# RIAA.net
KiCad netlist of a schematic drawn in Altium Designer
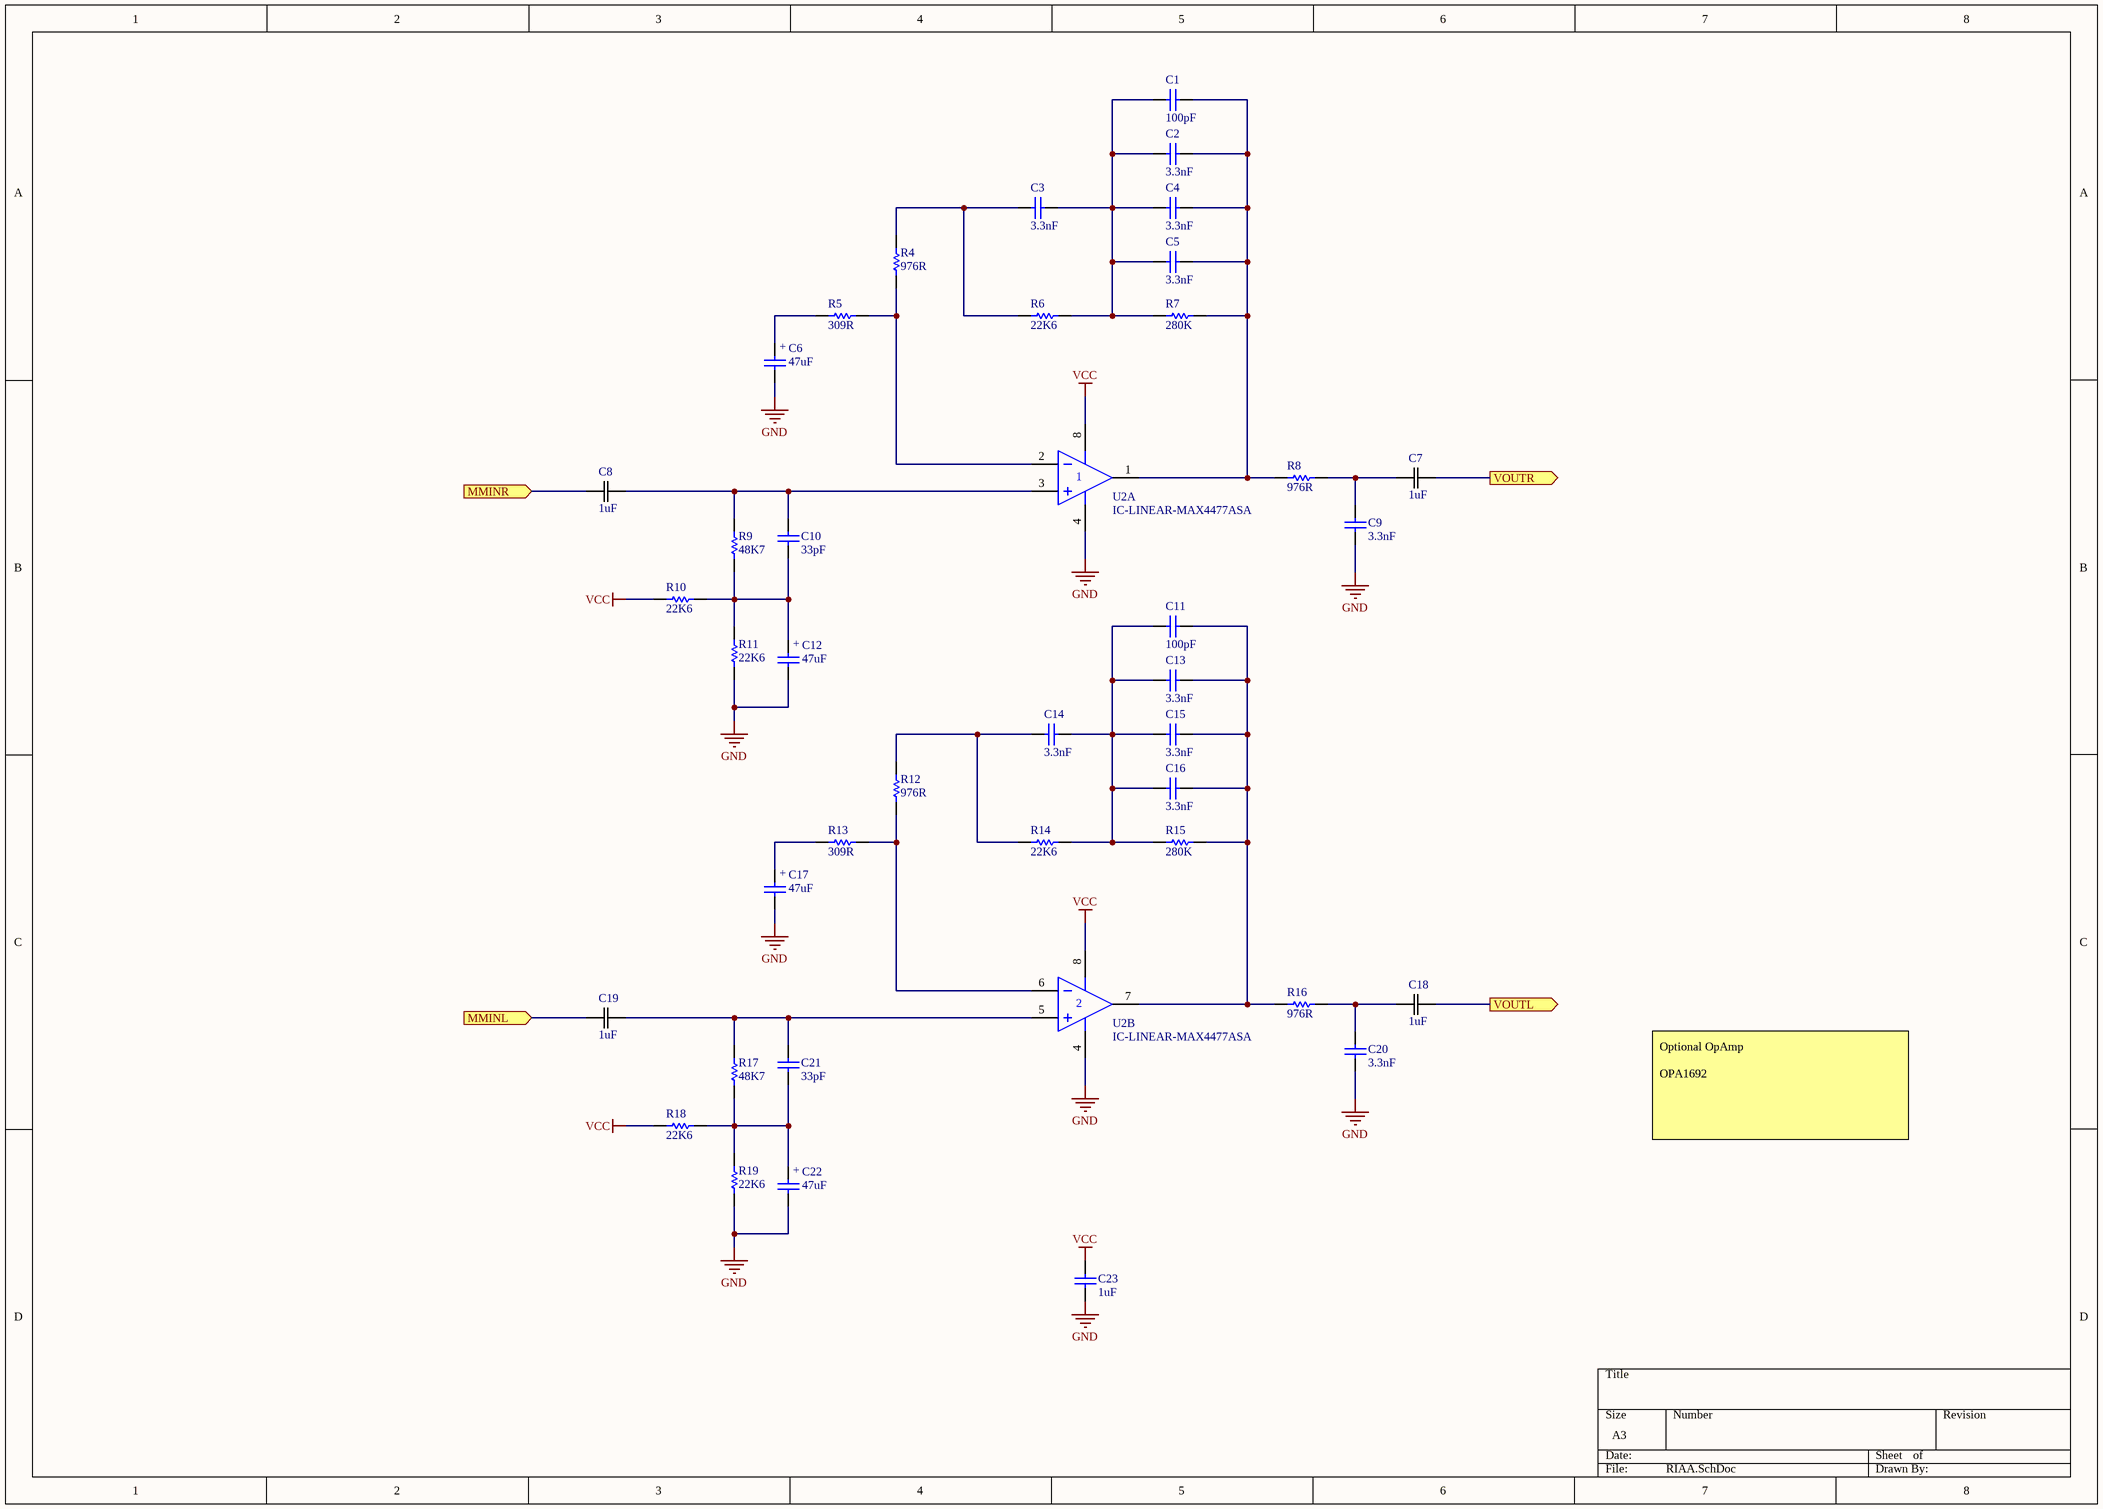
[diagram p0: RIAA.SchDoc]

(export (version "E")
  (design (tool "Eeschema 10.0.6"))
  (components
    (comp (ref "C1")
      (value "100pF")
      (footprint "CAPC0402(1005)33_L")
      (description "0402 100pF ±5% 50V C0G，NP0")
      (fields (field (name "MPN") "0402CG101J500NT") (field (name "VOLTAGE") "50V"))
      (libsource (lib "seeed") (part "CAP_100pF_0402"))
    )
    (comp (ref "C2")
      (value "3.3nF")
      (footprint "CAPC0603(1608)55_L")
      (description "0603 3.3nF ±5% 50V C0G(NPO) H=0.8mm")
      (fields (field (name "MPN") "CL10C332JB8NFNC") (field (name "VOLTAGE") "50V"))
      (libsource (lib "seeed") (part "CAP_3.3nF_0603"))
    )
    (comp (ref "C3")
      (value "3.3nF")
      (footprint "CAPC0603(1608)55_L")
      (description "0603 3.3nF ±5% 50V C0G(NPO) H=0.8mm")
      (fields (field (name "MPN") "CL10C332JB8NFNC") (field (name "VOLTAGE") "50V"))
      (libsource (lib "seeed") (part "CAP_3.3nF_0603"))
    )
    (comp (ref "C4")
      (value "3.3nF")
      (footprint "CAPC0603(1608)55_L")
      (description "0603 3.3nF ±5% 50V C0G(NPO) H=0.8mm")
      (fields (field (name "MPN") "CL10C332JB8NFNC") (field (name "VOLTAGE") "50V"))
      (libsource (lib "seeed") (part "CAP_3.3nF_0603"))
    )
    (comp (ref "C5")
      (value "3.3nF")
      (footprint "CAPC0603(1608)55_L")
      (description "0603 3.3nF ±5% 50V C0G(NPO) H=0.8mm")
      (fields (field (name "MPN") "CL10C332JB8NFNC") (field (name "VOLTAGE") "50V"))
      (libsource (lib "seeed") (part "CAP_3.3nF_0603"))
    )
    (comp (ref "C6")
      (value "47uF")
      (footprint "CAPPM3216X180N")
      (description "47µF ±10% 6.3V ESR=1.6Ω@100kHz")
      (fields (field (name "MPN") "TAJA476K006RNJ") (field (name "VOLTAGE") "6.3V"))
      (libsource (lib "seeed") (part "CAP_47uF_6.3V_1206"))
    )
    (comp (ref "C7")
      (value "1uF")
      (footprint "CAP_ECPU_G2")
      (description "1µF Film Capacitor  16V Acrylic, Metallized - Stacked 1210 (3225 Metric)")
      (fields (field (name "MPN") "ECP-U1C105MA5"))
      (libsource (lib "micun") (part "CAP-ECP-U1C105MA5"))
    )
    (comp (ref "C8")
      (value "1uF")
      (footprint "CAP_ECPU_G2")
      (description "1µF Film Capacitor  16V Acrylic, Metallized - Stacked 1210 (3225 Metric)")
      (fields (field (name "MPN") "ECP-U1C105MA5"))
      (libsource (lib "micun") (part "CAP-ECP-U1C105MA5"))
    )
    (comp (ref "C9")
      (value "3.3nF")
      (footprint "CAPC0603(1608)55_L")
      (description "0603 3.3nF ±5% 50V C0G(NPO) H=0.8mm")
      (fields (field (name "MPN") "CL10C332JB8NFNC") (field (name "VOLTAGE") "50V"))
      (libsource (lib "seeed") (part "CAP_3.3nF_0603"))
    )
    (comp (ref "C10")
      (value "33pF")
      (footprint "CAPC0402(1005)33_L")
      (description "0402 33PF ±5% 50V NPO")
      (fields (field (name "MPN") "CC0402JRNPO9BN330") (field (name "VOLTAGE") "50V"))
      (libsource (lib "seeed") (part "CAP_33pF_0402"))
    )
    (comp (ref "C11")
      (value "100pF")
      (footprint "CAPC0402(1005)33_L")
      (description "0402 100pF ±5% 50V C0G，NP0")
      (fields (field (name "MPN") "0402CG101J500NT") (field (name "VOLTAGE") "50V"))
      (libsource (lib "seeed") (part "CAP_100pF_0402"))
    )
    (comp (ref "C12")
      (value "47uF")
      (footprint "CAPPM3216X180N")
      (description "47µF ±10% 6.3V ESR=1.6Ω@100kHz")
      (fields (field (name "MPN") "TAJA476K006RNJ") (field (name "VOLTAGE") "6.3V"))
      (libsource (lib "seeed") (part "CAP_47uF_6.3V_1206"))
    )
    (comp (ref "C13")
      (value "3.3nF")
      (footprint "CAPC0603(1608)55_L")
      (description "0603 3.3nF ±5% 50V C0G(NPO) H=0.8mm")
      (fields (field (name "MPN") "CL10C332JB8NFNC") (field (name "VOLTAGE") "50V"))
      (libsource (lib "seeed") (part "CAP_3.3nF_0603"))
    )
    (comp (ref "C14")
      (value "3.3nF")
      (footprint "CAPC0603(1608)55_L")
      (description "0603 3.3nF ±5% 50V C0G(NPO) H=0.8mm")
      (fields (field (name "MPN") "CL10C332JB8NFNC") (field (name "VOLTAGE") "50V"))
      (libsource (lib "seeed") (part "CAP_3.3nF_0603"))
    )
    (comp (ref "C15")
      (value "3.3nF")
      (footprint "CAPC0603(1608)55_L")
      (description "0603 3.3nF ±5% 50V C0G(NPO) H=0.8mm")
      (fields (field (name "MPN") "CL10C332JB8NFNC") (field (name "VOLTAGE") "50V"))
      (libsource (lib "seeed") (part "CAP_3.3nF_0603"))
    )
    (comp (ref "C16")
      (value "3.3nF")
      (footprint "CAPC0603(1608)55_L")
      (description "0603 3.3nF ±5% 50V C0G(NPO) H=0.8mm")
      (fields (field (name "MPN") "CL10C332JB8NFNC") (field (name "VOLTAGE") "50V"))
      (libsource (lib "seeed") (part "CAP_3.3nF_0603"))
    )
    (comp (ref "C17")
      (value "47uF")
      (footprint "CAPPM3216X180N")
      (description "47µF ±10% 6.3V ESR=1.6Ω@100kHz")
      (fields (field (name "MPN") "TAJA476K006RNJ") (field (name "VOLTAGE") "6.3V"))
      (libsource (lib "seeed") (part "CAP_47uF_6.3V_1206"))
    )
    (comp (ref "C18")
      (value "1uF")
      (footprint "CAP_ECPU_G2")
      (description "1µF Film Capacitor  16V Acrylic, Metallized - Stacked 1210 (3225 Metric)")
      (fields (field (name "MPN") "ECP-U1C105MA5"))
      (libsource (lib "micun") (part "CAP-ECP-U1C105MA5"))
    )
    (comp (ref "C19")
      (value "1uF")
      (footprint "CAP_ECPU_G2")
      (description "1µF Film Capacitor  16V Acrylic, Metallized - Stacked 1210 (3225 Metric)")
      (fields (field (name "MPN") "ECP-U1C105MA5"))
      (libsource (lib "micun") (part "CAP-ECP-U1C105MA5"))
    )
    (comp (ref "C20")
      (value "3.3nF")
      (footprint "CAPC0603(1608)55_L")
      (description "0603 3.3nF ±5% 50V C0G(NPO) H=0.8mm")
      (fields (field (name "MPN") "CL10C332JB8NFNC") (field (name "VOLTAGE") "50V"))
      (libsource (lib "seeed") (part "CAP_3.3nF_0603"))
    )
    (comp (ref "C21")
      (value "33pF")
      (footprint "CAPC0402(1005)33_L")
      (description "0402 33PF ±5% 50V NPO")
      (fields (field (name "MPN") "CC0402JRNPO9BN330") (field (name "VOLTAGE") "50V"))
      (libsource (lib "seeed") (part "CAP_33pF_0402"))
    )
    (comp (ref "C22")
      (value "47uF")
      (footprint "CAPPM3216X180N")
      (description "47µF ±10% 6.3V ESR=1.6Ω@100kHz")
      (fields (field (name "MPN") "TAJA476K006RNJ") (field (name "VOLTAGE") "6.3V"))
      (libsource (lib "seeed") (part "CAP_47uF_6.3V_1206"))
    )
    (comp (ref "C23")
      (value "1uF")
      (footprint "CAPC0402(1005)33_L")
      (description "0402 1μF ±10% 16V X5R")
      (fields (field (name "MPN") "GRM155R61C105KA12D") (field (name "VOLTAGE") "10V"))
      (libsource (lib "seeed") (part "CAP_1uF_0402"))
    )
    (comp (ref "R4")
      (value "976R")
      (footprint "RESC0402(1005)_L")
      (description "0402 976Ω ±1% 1/16W")
      (fields (field (name "TOLERANCE") "1%") (field (name "POWER") "62.5mW"))
      (libsource (lib "seeed") (part "RES_976R_0402"))
    )
    (comp (ref "R5")
      (value "309R")
      (footprint "RESC0402(1005)_L")
      (description "0402 309Ω ±1% 1/16W")
      (fields (field (name "TOLERANCE") "1%") (field (name "POWER") "62.5mW"))
      (libsource (lib "seeed") (part "RES_309R_0402"))
    )
    (comp (ref "R6")
      (value "22K6")
      (footprint "RESC0402(1005)_L")
      (description "0402 22.6KΩ ±1% 1/16W")
      (fields (field (name "TOLERANCE") "1%") (field (name "POWER") "62.5mW"))
      (libsource (lib "seeed") (part "RES_22K6_0402"))
    )
    (comp (ref "R7")
      (value "280K")
      (footprint "RESC0402(1005)_L")
      (description "0402 280KΩ ±1% 1/16W")
      (fields (field (name "TOLERANCE") "1%") (field (name "POWER") "62.5mW"))
      (libsource (lib "seeed") (part "RES_280K_0402"))
    )
    (comp (ref "R8")
      (value "976R")
      (footprint "RESC0402(1005)_L")
      (description "0402 976Ω ±1% 1/16W")
      (fields (field (name "TOLERANCE") "1%") (field (name "POWER") "62.5mW"))
      (libsource (lib "seeed") (part "RES_976R_0402"))
    )
    (comp (ref "R9")
      (value "48K7")
      (footprint "RESC0402(1005)_L")
      (description "0402 48.7KΩ ±1% 1/16W")
      (fields (field (name "TOLERANCE") "1%") (field (name "POWER") "62.5mW"))
      (libsource (lib "seeed") (part "RES_48K7_0402"))
    )
    (comp (ref "R10")
      (value "22K6")
      (footprint "RESC0402(1005)_L")
      (description "0402 22.6KΩ ±1% 1/16W")
      (fields (field (name "TOLERANCE") "1%") (field (name "POWER") "62.5mW"))
      (libsource (lib "seeed") (part "RES_22K6_0402"))
    )
    (comp (ref "R11")
      (value "22K6")
      (footprint "RESC0402(1005)_L")
      (description "0402 22.6KΩ ±1% 1/16W")
      (fields (field (name "TOLERANCE") "1%") (field (name "POWER") "62.5mW"))
      (libsource (lib "seeed") (part "RES_22K6_0402"))
    )
    (comp (ref "R12")
      (value "976R")
      (footprint "RESC0402(1005)_L")
      (description "0402 976Ω ±1% 1/16W")
      (fields (field (name "TOLERANCE") "1%") (field (name "POWER") "62.5mW"))
      (libsource (lib "seeed") (part "RES_976R_0402"))
    )
    (comp (ref "R13")
      (value "309R")
      (footprint "RESC0402(1005)_L")
      (description "0402 309Ω ±1% 1/16W")
      (fields (field (name "TOLERANCE") "1%") (field (name "POWER") "62.5mW"))
      (libsource (lib "seeed") (part "RES_309R_0402"))
    )
    (comp (ref "R14")
      (value "22K6")
      (footprint "RESC0402(1005)_L")
      (description "0402 22.6KΩ ±1% 1/16W")
      (fields (field (name "TOLERANCE") "1%") (field (name "POWER") "62.5mW"))
      (libsource (lib "seeed") (part "RES_22K6_0402"))
    )
    (comp (ref "R15")
      (value "280K")
      (footprint "RESC0402(1005)_L")
      (description "0402 280KΩ ±1% 1/16W")
      (fields (field (name "TOLERANCE") "1%") (field (name "POWER") "62.5mW"))
      (libsource (lib "seeed") (part "RES_280K_0402"))
    )
    (comp (ref "R16")
      (value "976R")
      (footprint "RESC0402(1005)_L")
      (description "0402 976Ω ±1% 1/16W")
      (fields (field (name "TOLERANCE") "1%") (field (name "POWER") "62.5mW"))
      (libsource (lib "seeed") (part "RES_976R_0402"))
    )
    (comp (ref "R17")
      (value "48K7")
      (footprint "RESC0402(1005)_L")
      (description "0402 48.7KΩ ±1% 1/16W")
      (fields (field (name "TOLERANCE") "1%") (field (name "POWER") "62.5mW"))
      (libsource (lib "seeed") (part "RES_48K7_0402"))
    )
    (comp (ref "R18")
      (value "22K6")
      (footprint "RESC0402(1005)_L")
      (description "0402 22.6KΩ ±1% 1/16W")
      (fields (field (name "TOLERANCE") "1%") (field (name "POWER") "62.5mW"))
      (libsource (lib "seeed") (part "RES_22K6_0402"))
    )
    (comp (ref "R19")
      (value "22K6")
      (footprint "RESC0402(1005)_L")
      (description "0402 22.6KΩ ±1% 1/16W")
      (fields (field (name "TOLERANCE") "1%") (field (name "POWER") "62.5mW"))
      (libsource (lib "seeed") (part "RES_22K6_0402"))
    )
    (comp (ref "U2")
      (value "IC-LINEAR-MAX4477ASA")
      (footprint "SOIC8_N")
      (description "Dual Rail-to-Rail output  Low-Power Operational Amplifier")
      (fields (field (name "MPN") "MAX4477ASA+"))
      (libsource (lib "micun") (part "IC-LINEAR-MAX4477ASA"))
    )
  )
  (nets
    (net (code "1") (name "/MMINL") (class "Default")
      (node (ref "C19") (pin "1") (pinfunction "1_1") (pintype "passive"))
    )
    (net (code "2") (name "/MMINR") (class "Default")
      (node (ref "C8") (pin "1") (pinfunction "1_1") (pintype "passive"))
    )
    (net (code "3") (name "/VOUTL") (class "Default")
      (node (ref "C18") (pin "2") (pinfunction "2_2") (pintype "passive"))
    )
    (net (code "4") (name "/VOUTR") (class "Default")
      (node (ref "C7") (pin "2") (pinfunction "2_2") (pintype "passive"))
    )
    (net (code "5") (name "GND") (class "Default")
      (node (ref "C12") (pin "2") (pinfunction "2_2") (pintype "passive"))
      (node (ref "C17") (pin "2") (pinfunction "2_2") (pintype "passive"))
      (node (ref "C20") (pin "1") (pinfunction "1_1") (pintype "passive"))
      (node (ref "C22") (pin "2") (pinfunction "2_2") (pintype "passive"))
      (node (ref "C23") (pin "1") (pinfunction "1_1") (pintype "passive"))
      (node (ref "C6") (pin "2") (pinfunction "2_2") (pintype "passive"))
      (node (ref "C9") (pin "1") (pinfunction "1_1") (pintype "passive"))
      (node (ref "R11") (pin "2") (pinfunction "2_2") (pintype "passive"))
      (node (ref "R19") (pin "2") (pinfunction "2_2") (pintype "passive"))
      (node (ref "U2") (pin "4") (pinfunction "V-_4") (pintype "power_in"))
    )
    (net (code "6") (name "Net-(C1-Pad1)") (class "Default")
      (node (ref "C1") (pin "1") (pinfunction "1_1") (pintype "passive"))
      (node (ref "C2") (pin "1") (pinfunction "1_1") (pintype "passive"))
      (node (ref "C3") (pin "2") (pinfunction "2_2") (pintype "passive"))
      (node (ref "C4") (pin "1") (pinfunction "1_1") (pintype "passive"))
      (node (ref "C5") (pin "1") (pinfunction "1_1") (pintype "passive"))
      (node (ref "R6") (pin "2") (pinfunction "2_2") (pintype "passive"))
      (node (ref "R7") (pin "1") (pinfunction "1_1") (pintype "passive"))
    )
    (net (code "7") (name "Net-(C3-Pad1)") (class "Default")
      (node (ref "C3") (pin "1") (pinfunction "1_1") (pintype "passive"))
      (node (ref "R4") (pin "1") (pinfunction "1_1") (pintype "passive"))
      (node (ref "R6") (pin "1") (pinfunction "1_1") (pintype "passive"))
    )
    (net (code "8") (name "Net-(C6-Pad1)") (class "Default")
      (node (ref "C6") (pin "1") (pinfunction "1_1") (pintype "passive"))
      (node (ref "R5") (pin "1") (pinfunction "1_1") (pintype "passive"))
    )
    (net (code "9") (name "Net-(C7-Pad1)") (class "Default")
      (node (ref "C7") (pin "1") (pinfunction "1_1") (pintype "passive"))
      (node (ref "C9") (pin "2") (pinfunction "2_2") (pintype "passive"))
      (node (ref "R8") (pin "2") (pinfunction "2_2") (pintype "passive"))
    )
    (net (code "10") (name "Net-(C10-Pad2)") (class "Default")
      (node (ref "C10") (pin "2") (pinfunction "2_2") (pintype "passive"))
      (node (ref "C12") (pin "1") (pinfunction "1_1") (pintype "passive"))
      (node (ref "R10") (pin "2") (pinfunction "2_2") (pintype "passive"))
      (node (ref "R11") (pin "1") (pinfunction "1_1") (pintype "passive"))
      (node (ref "R9") (pin "2") (pinfunction "2_2") (pintype "passive"))
    )
    (net (code "11") (name "Net-(C11-Pad1)") (class "Default")
      (node (ref "C11") (pin "1") (pinfunction "1_1") (pintype "passive"))
      (node (ref "C13") (pin "1") (pinfunction "1_1") (pintype "passive"))
      (node (ref "C14") (pin "2") (pinfunction "2_2") (pintype "passive"))
      (node (ref "C15") (pin "1") (pinfunction "1_1") (pintype "passive"))
      (node (ref "C16") (pin "1") (pinfunction "1_1") (pintype "passive"))
      (node (ref "R14") (pin "2") (pinfunction "2_2") (pintype "passive"))
      (node (ref "R15") (pin "1") (pinfunction "1_1") (pintype "passive"))
    )
    (net (code "12") (name "Net-(C14-Pad1)") (class "Default")
      (node (ref "C14") (pin "1") (pinfunction "1_1") (pintype "passive"))
      (node (ref "R12") (pin "1") (pinfunction "1_1") (pintype "passive"))
      (node (ref "R14") (pin "1") (pinfunction "1_1") (pintype "passive"))
    )
    (net (code "13") (name "Net-(C17-Pad1)") (class "Default")
      (node (ref "C17") (pin "1") (pinfunction "1_1") (pintype "passive"))
      (node (ref "R13") (pin "1") (pinfunction "1_1") (pintype "passive"))
    )
    (net (code "14") (name "Net-(C18-Pad1)") (class "Default")
      (node (ref "C18") (pin "1") (pinfunction "1_1") (pintype "passive"))
      (node (ref "C20") (pin "2") (pinfunction "2_2") (pintype "passive"))
      (node (ref "R16") (pin "2") (pinfunction "2_2") (pintype "passive"))
    )
    (net (code "15") (name "Net-(C21-Pad2)") (class "Default")
      (node (ref "C21") (pin "2") (pinfunction "2_2") (pintype "passive"))
      (node (ref "C22") (pin "1") (pinfunction "1_1") (pintype "passive"))
      (node (ref "R17") (pin "2") (pinfunction "2_2") (pintype "passive"))
      (node (ref "R18") (pin "2") (pinfunction "2_2") (pintype "passive"))
      (node (ref "R19") (pin "1") (pinfunction "1_1") (pintype "passive"))
    )
    (net (code "16") (name "Net-(U2A-IN1+)") (class "Default")
      (node (ref "C10") (pin "1") (pinfunction "1_1") (pintype "passive"))
      (node (ref "C8") (pin "2") (pinfunction "2_2") (pintype "passive"))
      (node (ref "R9") (pin "1") (pinfunction "1_1") (pintype "passive"))
      (node (ref "U2") (pin "3") (pinfunction "IN1+_3") (pintype "passive"))
    )
    (net (code "17") (name "Net-(U2A-IN1-)") (class "Default")
      (node (ref "R4") (pin "2") (pinfunction "2_2") (pintype "passive"))
      (node (ref "R5") (pin "2") (pinfunction "2_2") (pintype "passive"))
      (node (ref "U2") (pin "2") (pinfunction "IN1-_2") (pintype "passive"))
    )
    (net (code "18") (name "Net-(U2A-OUT1)") (class "Default")
      (node (ref "C1") (pin "2") (pinfunction "2_2") (pintype "passive"))
      (node (ref "C2") (pin "2") (pinfunction "2_2") (pintype "passive"))
      (node (ref "C4") (pin "2") (pinfunction "2_2") (pintype "passive"))
      (node (ref "C5") (pin "2") (pinfunction "2_2") (pintype "passive"))
      (node (ref "R7") (pin "2") (pinfunction "2_2") (pintype "passive"))
      (node (ref "R8") (pin "1") (pinfunction "1_1") (pintype "passive"))
      (node (ref "U2") (pin "1") (pinfunction "OUT1_1") (pintype "passive"))
    )
    (net (code "19") (name "Net-(U2B-IN2+)") (class "Default")
      (node (ref "C19") (pin "2") (pinfunction "2_2") (pintype "passive"))
      (node (ref "C21") (pin "1") (pinfunction "1_1") (pintype "passive"))
      (node (ref "R17") (pin "1") (pinfunction "1_1") (pintype "passive"))
      (node (ref "U2") (pin "5") (pinfunction "IN2+_5") (pintype "passive"))
    )
    (net (code "20") (name "Net-(U2B-IN2-)") (class "Default")
      (node (ref "R12") (pin "2") (pinfunction "2_2") (pintype "passive"))
      (node (ref "R13") (pin "2") (pinfunction "2_2") (pintype "passive"))
      (node (ref "U2") (pin "6") (pinfunction "IN2-_6") (pintype "passive"))
    )
    (net (code "21") (name "Net-(U2B-OUT2)") (class "Default")
      (node (ref "C11") (pin "2") (pinfunction "2_2") (pintype "passive"))
      (node (ref "C13") (pin "2") (pinfunction "2_2") (pintype "passive"))
      (node (ref "C15") (pin "2") (pinfunction "2_2") (pintype "passive"))
      (node (ref "C16") (pin "2") (pinfunction "2_2") (pintype "passive"))
      (node (ref "R15") (pin "2") (pinfunction "2_2") (pintype "passive"))
      (node (ref "R16") (pin "1") (pinfunction "1_1") (pintype "passive"))
      (node (ref "U2") (pin "7") (pinfunction "OUT2_7") (pintype "passive"))
    )
    (net (code "22") (name "VCC") (class "Default")
      (node (ref "C23") (pin "2") (pinfunction "2_2") (pintype "passive"))
      (node (ref "R10") (pin "1") (pinfunction "1_1") (pintype "passive"))
      (node (ref "R18") (pin "1") (pinfunction "1_1") (pintype "passive"))
      (node (ref "U2") (pin "8") (pinfunction "V+_8") (pintype "power_in"))
    )
  )
)
